# KwadraLampaBT.net
KiCad netlist of a schematic drawn in EAGLE
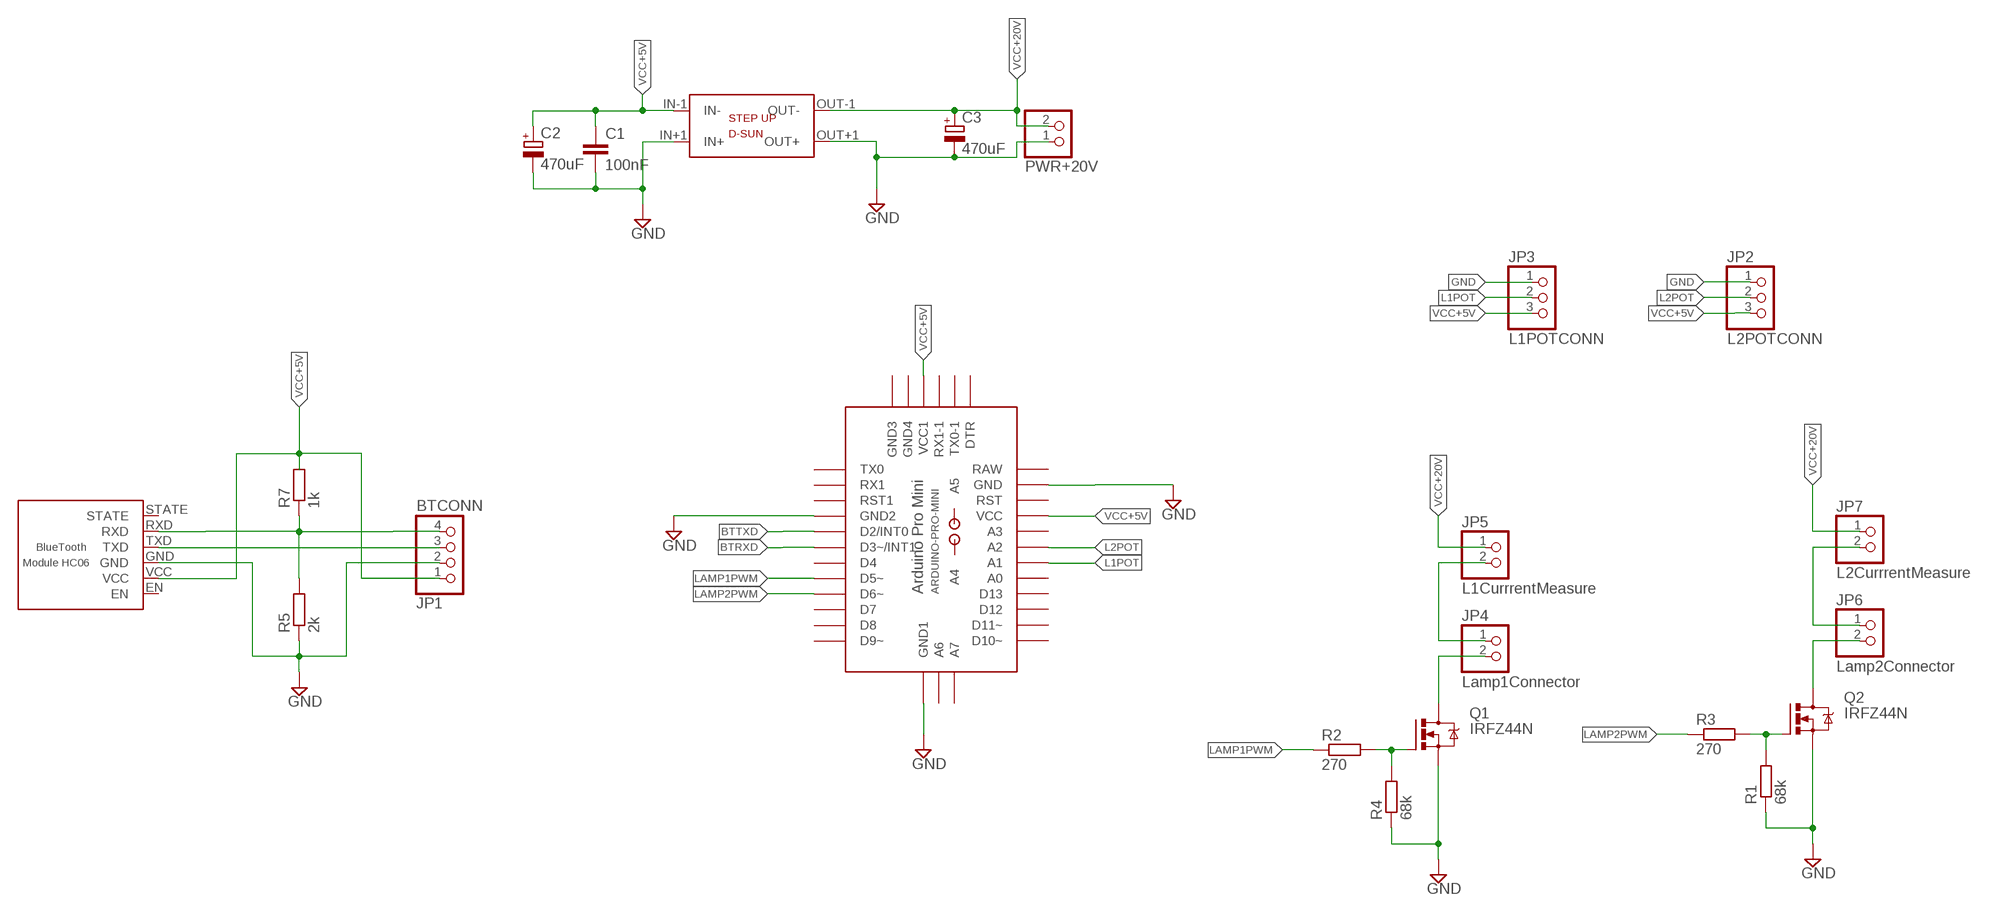
[diagram p0: schematic, sheet 1]

(export (version "E")
  (design (tool "Eeschema 10.0.6"))
  (components
    (comp (ref "C1")
      (value "100nF")
      (footprint "eagle-import:C025-025X050")
      (libsource (lib "eagle-import") (part "C_CERAMIC_2.5X50"))
    )
    (comp (ref "C2")
      (value "470uF")
      (footprint "eagle-import:C_E_R5-FI13_ELECTROLYTIC")
      (libsource (lib "eagle-import") (part "C_ELECTROLYTIC_3"))
    )
    (comp (ref "C3")
      (value "470uF")
      (footprint "eagle-import:C_E_R5-FI13_ELECTROLYTIC")
      (libsource (lib "eagle-import") (part "C_ELECTROLYTIC_3"))
    )
    (comp (ref "IC1")
      (value "HC06")
      (footprint "eagle-import:HC06")
      (libsource (lib "eagle-import") (part "HC06"))
    )
    (comp (ref "JP1")
      (value "BTCONN")
      (footprint "eagle-import:1X04")
      (libsource (lib "eagle-import") (part "PINHD-1X4"))
    )
    (comp (ref "JP2")
      (value "L2POTCONN")
      (footprint "eagle-import:1X03")
      (libsource (lib "eagle-import") (part "PINHD-1X3"))
    )
    (comp (ref "JP3")
      (value "L1POTCONN")
      (footprint "eagle-import:1X03")
      (libsource (lib "eagle-import") (part "PINHD-1X3"))
    )
    (comp (ref "JP4")
      (value "Lamp1Connector")
      (footprint "eagle-import:1X02")
      (libsource (lib "eagle-import") (part "PINHD-1X2"))
    )
    (comp (ref "JP5")
      (value "L1CurrrentMeasure")
      (footprint "eagle-import:1X02")
      (libsource (lib "eagle-import") (part "PINHD-1X2"))
    )
    (comp (ref "JP6")
      (value "Lamp2Connector")
      (footprint "eagle-import:1X02")
      (libsource (lib "eagle-import") (part "PINHD-1X2"))
    )
    (comp (ref "JP7")
      (value "L2CurrrentMeasure")
      (footprint "eagle-import:1X02")
      (libsource (lib "eagle-import") (part "PINHD-1X2"))
    )
    (comp (ref "PWR+20V")
      (value "PINHD-1X2")
      (footprint "eagle-import:1X02")
      (libsource (lib "eagle-import") (part "PINHD-1X2"))
    )
    (comp (ref "Q1")
      (value "IRFZ44N")
      (footprint "eagle-import:TO220AB-GDS-VERT")
      (libsource (lib "eagle-import") (part "IRFZ44NVERT"))
    )
    (comp (ref "Q2")
      (value "IRFZ44N")
      (footprint "eagle-import:TO220AB-GDS-VERT")
      (libsource (lib "eagle-import") (part "IRFZ44NVERT"))
    )
    (comp (ref "R1")
      (value "68k")
      (footprint "eagle-import:SMD1206")
      (libsource (lib "eagle-import") (part "R_SMD1206"))
    )
    (comp (ref "R2")
      (value "270")
      (footprint "eagle-import:SMD1206")
      (libsource (lib "eagle-import") (part "R_SMD1206"))
    )
    (comp (ref "R3")
      (value "270")
      (footprint "eagle-import:SMD1206")
      (libsource (lib "eagle-import") (part "R_SMD1206"))
    )
    (comp (ref "R4")
      (value "68k")
      (footprint "eagle-import:SMD1206")
      (libsource (lib "eagle-import") (part "R_SMD1206"))
    )
    (comp (ref "R5")
      (value "2k")
      (footprint "eagle-import:SMD1206")
      (libsource (lib "eagle-import") (part "R_SMD1206"))
    )
    (comp (ref "R7")
      (value "1k")
      (footprint "eagle-import:SMD1206")
      (libsource (lib "eagle-import") (part "R_SMD1206"))
    )
    (comp (ref "U$1")
      (value "ARDUINO-PRO-MINI")
      (footprint "eagle-import:ARDUINO-PRO-MINI")
      (libsource (lib "eagle-import") (part "ARDUINO-PRO-MINI"))
    )
    (comp (ref "U$2")
      (value "STEPUP_D-SUN")
      (footprint "eagle-import:STEPUP_D-SUN")
      (libsource (lib "eagle-import") (part "STEPUP_D-SUN"))
    )
  )
  (nets
    (net (code "1") (name "BTRXD") (class "Default")
      (node (ref "IC1") (pin "RXD") (pinfunction "RXD_RXD") (pintype "input"))
      (node (ref "JP1") (pin "4") (pinfunction "4_4") (pintype "passive"))
      (node (ref "R5") (pin "2") (pinfunction "2_2") (pintype "passive"))
      (node (ref "R7") (pin "1") (pinfunction "1_1") (pintype "passive"))
      (node (ref "U$1") (pin "D3") (pinfunction "D3~{/INT1}_D3") (pintype "bidirectional"))
    )
    (net (code "2") (name "BTTXD") (class "Default")
      (node (ref "IC1") (pin "TXD") (pinfunction "TXD_TXD") (pintype "output"))
      (node (ref "JP1") (pin "3") (pinfunction "3_3") (pintype "passive"))
      (node (ref "U$1") (pin "D2") (pinfunction "D2/INT0_D2") (pintype "bidirectional"))
    )
    (net (code "3") (name "GND") (class "Default")
      (node (ref "C1") (pin "2") (pinfunction "2_2") (pintype "passive"))
      (node (ref "C2") (pin "-") (pinfunction "-_-") (pintype "passive"))
      (node (ref "C3") (pin "-") (pinfunction "-_-") (pintype "passive"))
      (node (ref "IC1") (pin "GND") (pinfunction "GND_GND") (pintype "power_in"))
      (node (ref "JP1") (pin "2") (pinfunction "2_2") (pintype "passive"))
      (node (ref "JP2") (pin "1") (pinfunction "1_1") (pintype "passive"))
      (node (ref "JP3") (pin "1") (pinfunction "1_1") (pintype "passive"))
      (node (ref "PWR+20V") (pin "1") (pinfunction "1_1") (pintype "passive"))
      (node (ref "Q1") (pin "S") (pinfunction "S_S") (pintype "passive"))
      (node (ref "Q2") (pin "S") (pinfunction "S_S") (pintype "passive"))
      (node (ref "R1") (pin "1") (pinfunction "1_1") (pintype "passive"))
      (node (ref "R4") (pin "1") (pinfunction "1_1") (pintype "passive"))
      (node (ref "R5") (pin "1") (pinfunction "1_1") (pintype "passive"))
      (node (ref "U$1") (pin "GND") (pinfunction "GND_GND") (pintype "power_in"))
      (node (ref "U$1") (pin "GND1") (pinfunction "GND2_GND1") (pintype "power_in"))
      (node (ref "U$1") (pin "GND4") (pinfunction "GND1_GND4") (pintype "power_in"))
      (node (ref "U$2") (pin "IN+1") (pinfunction "IN+_IN+1") (pintype "bidirectional"))
      (node (ref "U$2") (pin "OUT+1") (pinfunction "OUT+_OUT+1") (pintype "bidirectional"))
    )
    (net (code "4") (name "L1POT") (class "Default")
      (node (ref "JP3") (pin "2") (pinfunction "2_2") (pintype "passive"))
      (node (ref "U$1") (pin "A1") (pinfunction "A1_A1") (pintype "bidirectional"))
    )
    (net (code "5") (name "L2POT") (class "Default")
      (node (ref "JP2") (pin "2") (pinfunction "2_2") (pintype "passive"))
      (node (ref "U$1") (pin "A2") (pinfunction "A2_A2") (pintype "bidirectional"))
    )
    (net (code "6") (name "LAMP1PWM") (class "Default")
      (node (ref "R2") (pin "1") (pinfunction "1_1") (pintype "passive"))
      (node (ref "U$1") (pin "D5") (pinfunction "D5~{}_D5") (pintype "bidirectional"))
    )
    (net (code "7") (name "LAMP2PWM") (class "Default")
      (node (ref "R3") (pin "1") (pinfunction "1_1") (pintype "passive"))
      (node (ref "U$1") (pin "D6") (pinfunction "D6~{}_D6") (pintype "bidirectional"))
    )
    (net (code "8") (name "Net-(JP4-Pad1)") (class "Default")
      (node (ref "JP4") (pin "1") (pinfunction "1_1") (pintype "passive"))
      (node (ref "JP5") (pin "2") (pinfunction "2_2") (pintype "passive"))
    )
    (net (code "9") (name "Net-(JP4-Pad2)") (class "Default")
      (node (ref "JP4") (pin "2") (pinfunction "2_2") (pintype "passive"))
      (node (ref "Q1") (pin "D") (pinfunction "D_D") (pintype "passive"))
    )
    (net (code "10") (name "Net-(JP6-Pad1)") (class "Default")
      (node (ref "JP6") (pin "1") (pinfunction "1_1") (pintype "passive"))
      (node (ref "JP7") (pin "2") (pinfunction "2_2") (pintype "passive"))
    )
    (net (code "11") (name "Net-(JP6-Pad2)") (class "Default")
      (node (ref "JP6") (pin "2") (pinfunction "2_2") (pintype "passive"))
      (node (ref "Q2") (pin "D") (pinfunction "D_D") (pintype "passive"))
    )
    (net (code "12") (name "Net-(Q1-PadG)") (class "Default")
      (node (ref "Q1") (pin "G") (pinfunction "G_G") (pintype "passive"))
      (node (ref "R2") (pin "2") (pinfunction "2_2") (pintype "passive"))
      (node (ref "R4") (pin "2") (pinfunction "2_2") (pintype "passive"))
    )
    (net (code "13") (name "Net-(Q2-PadG)") (class "Default")
      (node (ref "Q2") (pin "G") (pinfunction "G_G") (pintype "passive"))
      (node (ref "R1") (pin "2") (pinfunction "2_2") (pintype "passive"))
      (node (ref "R3") (pin "2") (pinfunction "2_2") (pintype "passive"))
    )
    (net (code "14") (name "VCC+5V") (class "Default")
      (node (ref "C1") (pin "1") (pinfunction "1_1") (pintype "passive"))
      (node (ref "C2") (pin "+") (pinfunction "+_+") (pintype "passive"))
      (node (ref "IC1") (pin "VCC") (pinfunction "VCC_VCC") (pintype "power_in"))
      (node (ref "JP1") (pin "1") (pinfunction "1_1") (pintype "passive"))
      (node (ref "JP2") (pin "3") (pinfunction "3_3") (pintype "passive"))
      (node (ref "JP3") (pin "3") (pinfunction "3_3") (pintype "passive"))
      (node (ref "R7") (pin "2") (pinfunction "2_2") (pintype "passive"))
      (node (ref "U$1") (pin "VCC") (pinfunction "VCC_VCC") (pintype "power_in"))
      (node (ref "U$1") (pin "VCC1") (pinfunction "VCC1_VCC1") (pintype "power_in"))
      (node (ref "U$2") (pin "IN-1") (pinfunction "IN-_IN-1") (pintype "bidirectional"))
    )
    (net (code "15") (name "VCC+20V") (class "Default")
      (node (ref "C3") (pin "+") (pinfunction "+_+") (pintype "passive"))
      (node (ref "JP5") (pin "1") (pinfunction "1_1") (pintype "passive"))
      (node (ref "JP7") (pin "1") (pinfunction "1_1") (pintype "passive"))
      (node (ref "PWR+20V") (pin "2") (pinfunction "2_2") (pintype "passive"))
      (node (ref "U$2") (pin "OUT-1") (pinfunction "OUT-_OUT-1") (pintype "bidirectional"))
    )
    (net (code "16") (name "unconnected-(IC1-PadEN)") (class "Default")
      (node (ref "IC1") (pin "EN") (pinfunction "EN_EN") (pintype "input"))
    )
    (net (code "17") (name "unconnected-(IC1-PadSTATE)") (class "Default")
      (node (ref "IC1") (pin "STATE") (pinfunction "STATE_STATE") (pintype "output"))
    )
    (net (code "18") (name "unconnected-(U$1-D9~{}-PadD9)") (class "Default")
      (node (ref "U$1") (pin "D9") (pinfunction "D9~{}_D9") (pintype "bidirectional"))
    )
    (net (code "19") (name "unconnected-(U$1-D10~{}-PadD10)") (class "Default")
      (node (ref "U$1") (pin "D10") (pinfunction "D10~{}_D10") (pintype "bidirectional"))
    )
    (net (code "20") (name "unconnected-(U$1-D11~{}-PadD11)") (class "Default")
      (node (ref "U$1") (pin "D11") (pinfunction "D11~{}_D11") (pintype "bidirectional"))
    )
    (net (code "21") (name "unconnected-(U$1-GND3-PadGND2)") (class "Default")
      (node (ref "U$1") (pin "GND2") (pinfunction "GND3_GND2") (pintype "bidirectional"))
    )
    (net (code "22") (name "unconnected-(U$1-GND4-PadGND3)") (class "Default")
      (node (ref "U$1") (pin "GND3") (pinfunction "GND4_GND3") (pintype "bidirectional"))
    )
    (net (code "23") (name "unconnected-(U$1-PadA0)") (class "Default")
      (node (ref "U$1") (pin "A0") (pinfunction "A0_A0") (pintype "bidirectional"))
    )
    (net (code "24") (name "unconnected-(U$1-PadA3)") (class "Default")
      (node (ref "U$1") (pin "A3") (pinfunction "A3_A3") (pintype "bidirectional"))
    )
    (net (code "25") (name "unconnected-(U$1-PadA4)") (class "Default")
      (node (ref "U$1") (pin "A4") (pinfunction "A4_A4") (pintype "bidirectional"))
    )
    (net (code "26") (name "unconnected-(U$1-PadA5)") (class "Default")
      (node (ref "U$1") (pin "A5") (pinfunction "A5_A5") (pintype "bidirectional"))
    )
    (net (code "27") (name "unconnected-(U$1-PadA6)") (class "Default")
      (node (ref "U$1") (pin "A6") (pinfunction "A6_A6") (pintype "bidirectional"))
    )
    (net (code "28") (name "unconnected-(U$1-PadA7)") (class "Default")
      (node (ref "U$1") (pin "A7") (pinfunction "A7_A7") (pintype "bidirectional"))
    )
    (net (code "29") (name "unconnected-(U$1-PadD4)") (class "Default")
      (node (ref "U$1") (pin "D4") (pinfunction "D4_D4") (pintype "bidirectional"))
    )
    (net (code "30") (name "unconnected-(U$1-PadD7)") (class "Default")
      (node (ref "U$1") (pin "D7") (pinfunction "D7_D7") (pintype "bidirectional"))
    )
    (net (code "31") (name "unconnected-(U$1-PadD8)") (class "Default")
      (node (ref "U$1") (pin "D8") (pinfunction "D8_D8") (pintype "bidirectional"))
    )
    (net (code "32") (name "unconnected-(U$1-PadD12)") (class "Default")
      (node (ref "U$1") (pin "D12") (pinfunction "D12_D12") (pintype "bidirectional"))
    )
    (net (code "33") (name "unconnected-(U$1-PadD13)") (class "Default")
      (node (ref "U$1") (pin "D13") (pinfunction "D13_D13") (pintype "bidirectional"))
    )
    (net (code "34") (name "unconnected-(U$1-PadDTR)") (class "Default")
      (node (ref "U$1") (pin "DTR") (pinfunction "DTR_DTR") (pintype "bidirectional"))
    )
    (net (code "35") (name "unconnected-(U$1-PadRAW)") (class "Default")
      (node (ref "U$1") (pin "RAW") (pinfunction "RAW_RAW") (pintype "bidirectional"))
    )
    (net (code "36") (name "unconnected-(U$1-PadRST)") (class "Default")
      (node (ref "U$1") (pin "RST") (pinfunction "RST_RST") (pintype "bidirectional"))
    )
    (net (code "37") (name "unconnected-(U$1-PadRST1)") (class "Default")
      (node (ref "U$1") (pin "RST1") (pinfunction "RST1_RST1") (pintype "bidirectional"))
    )
    (net (code "38") (name "unconnected-(U$1-PadRX1)") (class "Default")
      (node (ref "U$1") (pin "RX1") (pinfunction "RX1_RX1") (pintype "bidirectional"))
    )
    (net (code "39") (name "unconnected-(U$1-PadRX1-1)") (class "Default")
      (node (ref "U$1") (pin "RX1-1") (pinfunction "RX1-1_RX1-1") (pintype "bidirectional"))
    )
    (net (code "40") (name "unconnected-(U$1-PadTX0)") (class "Default")
      (node (ref "U$1") (pin "TX0") (pinfunction "TX0_TX0") (pintype "bidirectional"))
    )
    (net (code "41") (name "unconnected-(U$1-PadTX0-1)") (class "Default")
      (node (ref "U$1") (pin "TX0-1") (pinfunction "TX0-1_TX0-1") (pintype "bidirectional"))
    )
  )
)
